# Co-axial.net
KiCad netlist of a schematic drawn in Altium Designer
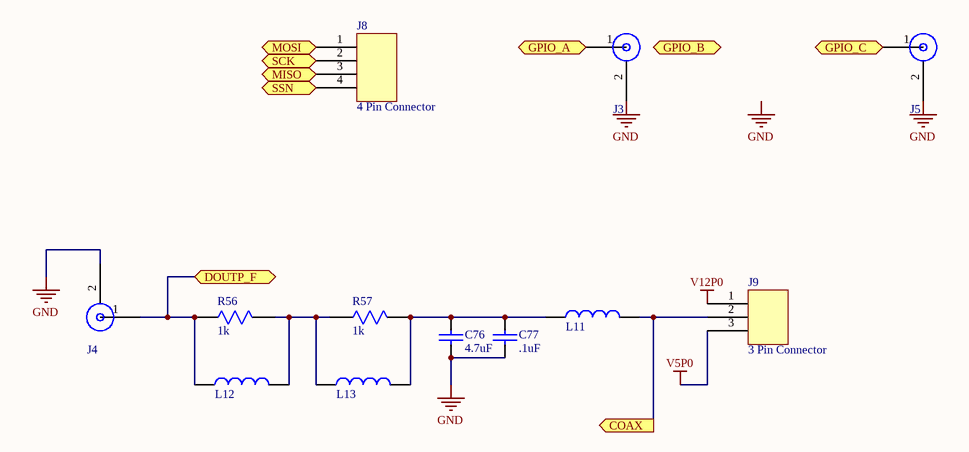
[diagram p0: Co-axial.SchDoc]

(export (version "E")
  (design (tool "Eeschema 10.0.6"))
  (components
    (comp (ref "C76")
      (value "4.7uF")
      (footprint "SMD Capacitor 0603")
      (libsource (lib "DA_Component_Library") (part "Capacitor"))
    )
    (comp (ref "C77")
      (value ".1uF")
      (footprint "SMD CAP 0402")
      (libsource (lib "DA_Component_Library") (part "Capacitor"))
    )
    (comp (ref "J3")
      (value "SMA")
      (footprint "SMA Right Angle Through Hole")
      (libsource (lib "DA_Component_Library") (part "SMA"))
    )
    (comp (ref "J4")
      (value "SMA")
      (footprint "SMA Right Angle Through Hole")
      (libsource (lib "DA_Component_Library") (part "SMA"))
    )
    (comp (ref "J5")
      (value "SMA")
      (footprint "SMA Right Angle Through Hole")
      (libsource (lib "DA_Component_Library") (part "SMA"))
    )
    (comp (ref "J8")
      (value "4 Pin Connector")
      (footprint "4Pin Verital 0.1\"")
      (libsource (lib "DA_Component_Library") (part "4 Pin Connector"))
    )
    (comp (ref "J9")
      (value "3 Pin Connector")
      (footprint "3Pin Verital 0.1\" JUMOER")
      (libsource (lib "DA_Component_Library") (part "3 Pin Connector"))
    )
    (comp (ref "L11")
      (value "Ferrite Bead")
      (footprint "BLM18KG601SN1D")
      (libsource (lib "DA_Component_Library") (part "Ferrite Bead"))
    )
    (comp (ref "L12")
      (value "Ferrite Bead")
      (footprint "CIG21L4R7MNE")
      (libsource (lib "DA_Component_Library") (part "Ferrite Bead"))
    )
    (comp (ref "L13")
      (value "Ferrite Bead")
      (footprint "CBC3225T101MR")
      (libsource (lib "DA_Component_Library") (part "Ferrite Bead"))
    )
    (comp (ref "R56")
      (value "1k")
      (footprint "SMD Resistor 0603")
      (libsource (lib "DA_Component_Library") (part "Resistor"))
    )
    (comp (ref "R57")
      (value "1k")
      (footprint "SMD Resistor 0603")
      (libsource (lib "DA_Component_Library") (part "Resistor"))
    )
  )
  (nets
    (net (code "1") (name "/COAX") (class "Default")
      (node (ref "J9") (pin "2") (pinfunction "2_2") (pintype "passive"))
      (node (ref "L11") (pin "2") (pinfunction "2_2") (pintype "passive"))
    )
    (net (code "2") (name "/DOUTP_F") (class "Default")
      (node (ref "J4") (pin "1") (pinfunction "1_1") (pintype "passive"))
      (node (ref "L12") (pin "1") (pinfunction "1_1") (pintype "passive"))
      (node (ref "R56") (pin "0") (pinfunction "0_0") (pintype "passive"))
    )
    (net (code "3") (name "/GPIO_A") (class "Default")
      (node (ref "J3") (pin "1") (pinfunction "1_1") (pintype "passive"))
    )
    (net (code "5") (name "/GPIO_C") (class "Default")
      (node (ref "J5") (pin "1") (pinfunction "1_1") (pintype "passive"))
    )
    (net (code "6") (name "/MISO") (class "Default")
      (node (ref "J8") (pin "3") (pinfunction "3_3") (pintype "passive"))
    )
    (net (code "7") (name "/MOSI") (class "Default")
      (node (ref "J8") (pin "1") (pinfunction "1_1") (pintype "passive"))
    )
    (net (code "8") (name "/SCK") (class "Default")
      (node (ref "J8") (pin "2") (pinfunction "2_2") (pintype "passive"))
    )
    (net (code "9") (name "/SSN") (class "Default")
      (node (ref "J8") (pin "4") (pinfunction "4_4") (pintype "passive"))
    )
    (net (code "10") (name "GND") (class "Default")
      (node (ref "C76") (pin "1") (pinfunction "1_1") (pintype "passive"))
      (node (ref "C77") (pin "1") (pinfunction "1_1") (pintype "passive"))
      (node (ref "J3") (pin "2") (pinfunction "2_2") (pintype "passive"))
      (node (ref "J4") (pin "2") (pinfunction "2_2") (pintype "passive"))
      (node (ref "J5") (pin "2") (pinfunction "2_2") (pintype "passive"))
    )
    (net (code "11") (name "Net-(C76-Pad0)") (class "Default")
      (node (ref "C76") (pin "0") (pinfunction "0_0") (pintype "passive"))
      (node (ref "C77") (pin "0") (pinfunction "0_0") (pintype "passive"))
      (node (ref "L11") (pin "1") (pinfunction "1_1") (pintype "passive"))
      (node (ref "L13") (pin "2") (pinfunction "2_2") (pintype "passive"))
      (node (ref "R57") (pin "1") (pinfunction "1_1") (pintype "passive"))
    )
    (net (code "12") (name "Net-(L12-Pad2)") (class "Default")
      (node (ref "L12") (pin "2") (pinfunction "2_2") (pintype "passive"))
      (node (ref "L13") (pin "1") (pinfunction "1_1") (pintype "passive"))
      (node (ref "R56") (pin "1") (pinfunction "1_1") (pintype "passive"))
      (node (ref "R57") (pin "0") (pinfunction "0_0") (pintype "passive"))
    )
    (net (code "13") (name "V5P0") (class "Default")
      (node (ref "J9") (pin "3") (pinfunction "3_3") (pintype "passive"))
    )
    (net (code "14") (name "V12P0") (class "Default")
      (node (ref "J9") (pin "1") (pinfunction "1_1") (pintype "passive"))
    )
  )
)
